# SCH_Senior_Transmitter_2026-03-29.net
KiCad netlist of a schematic drawn in EasyEDA
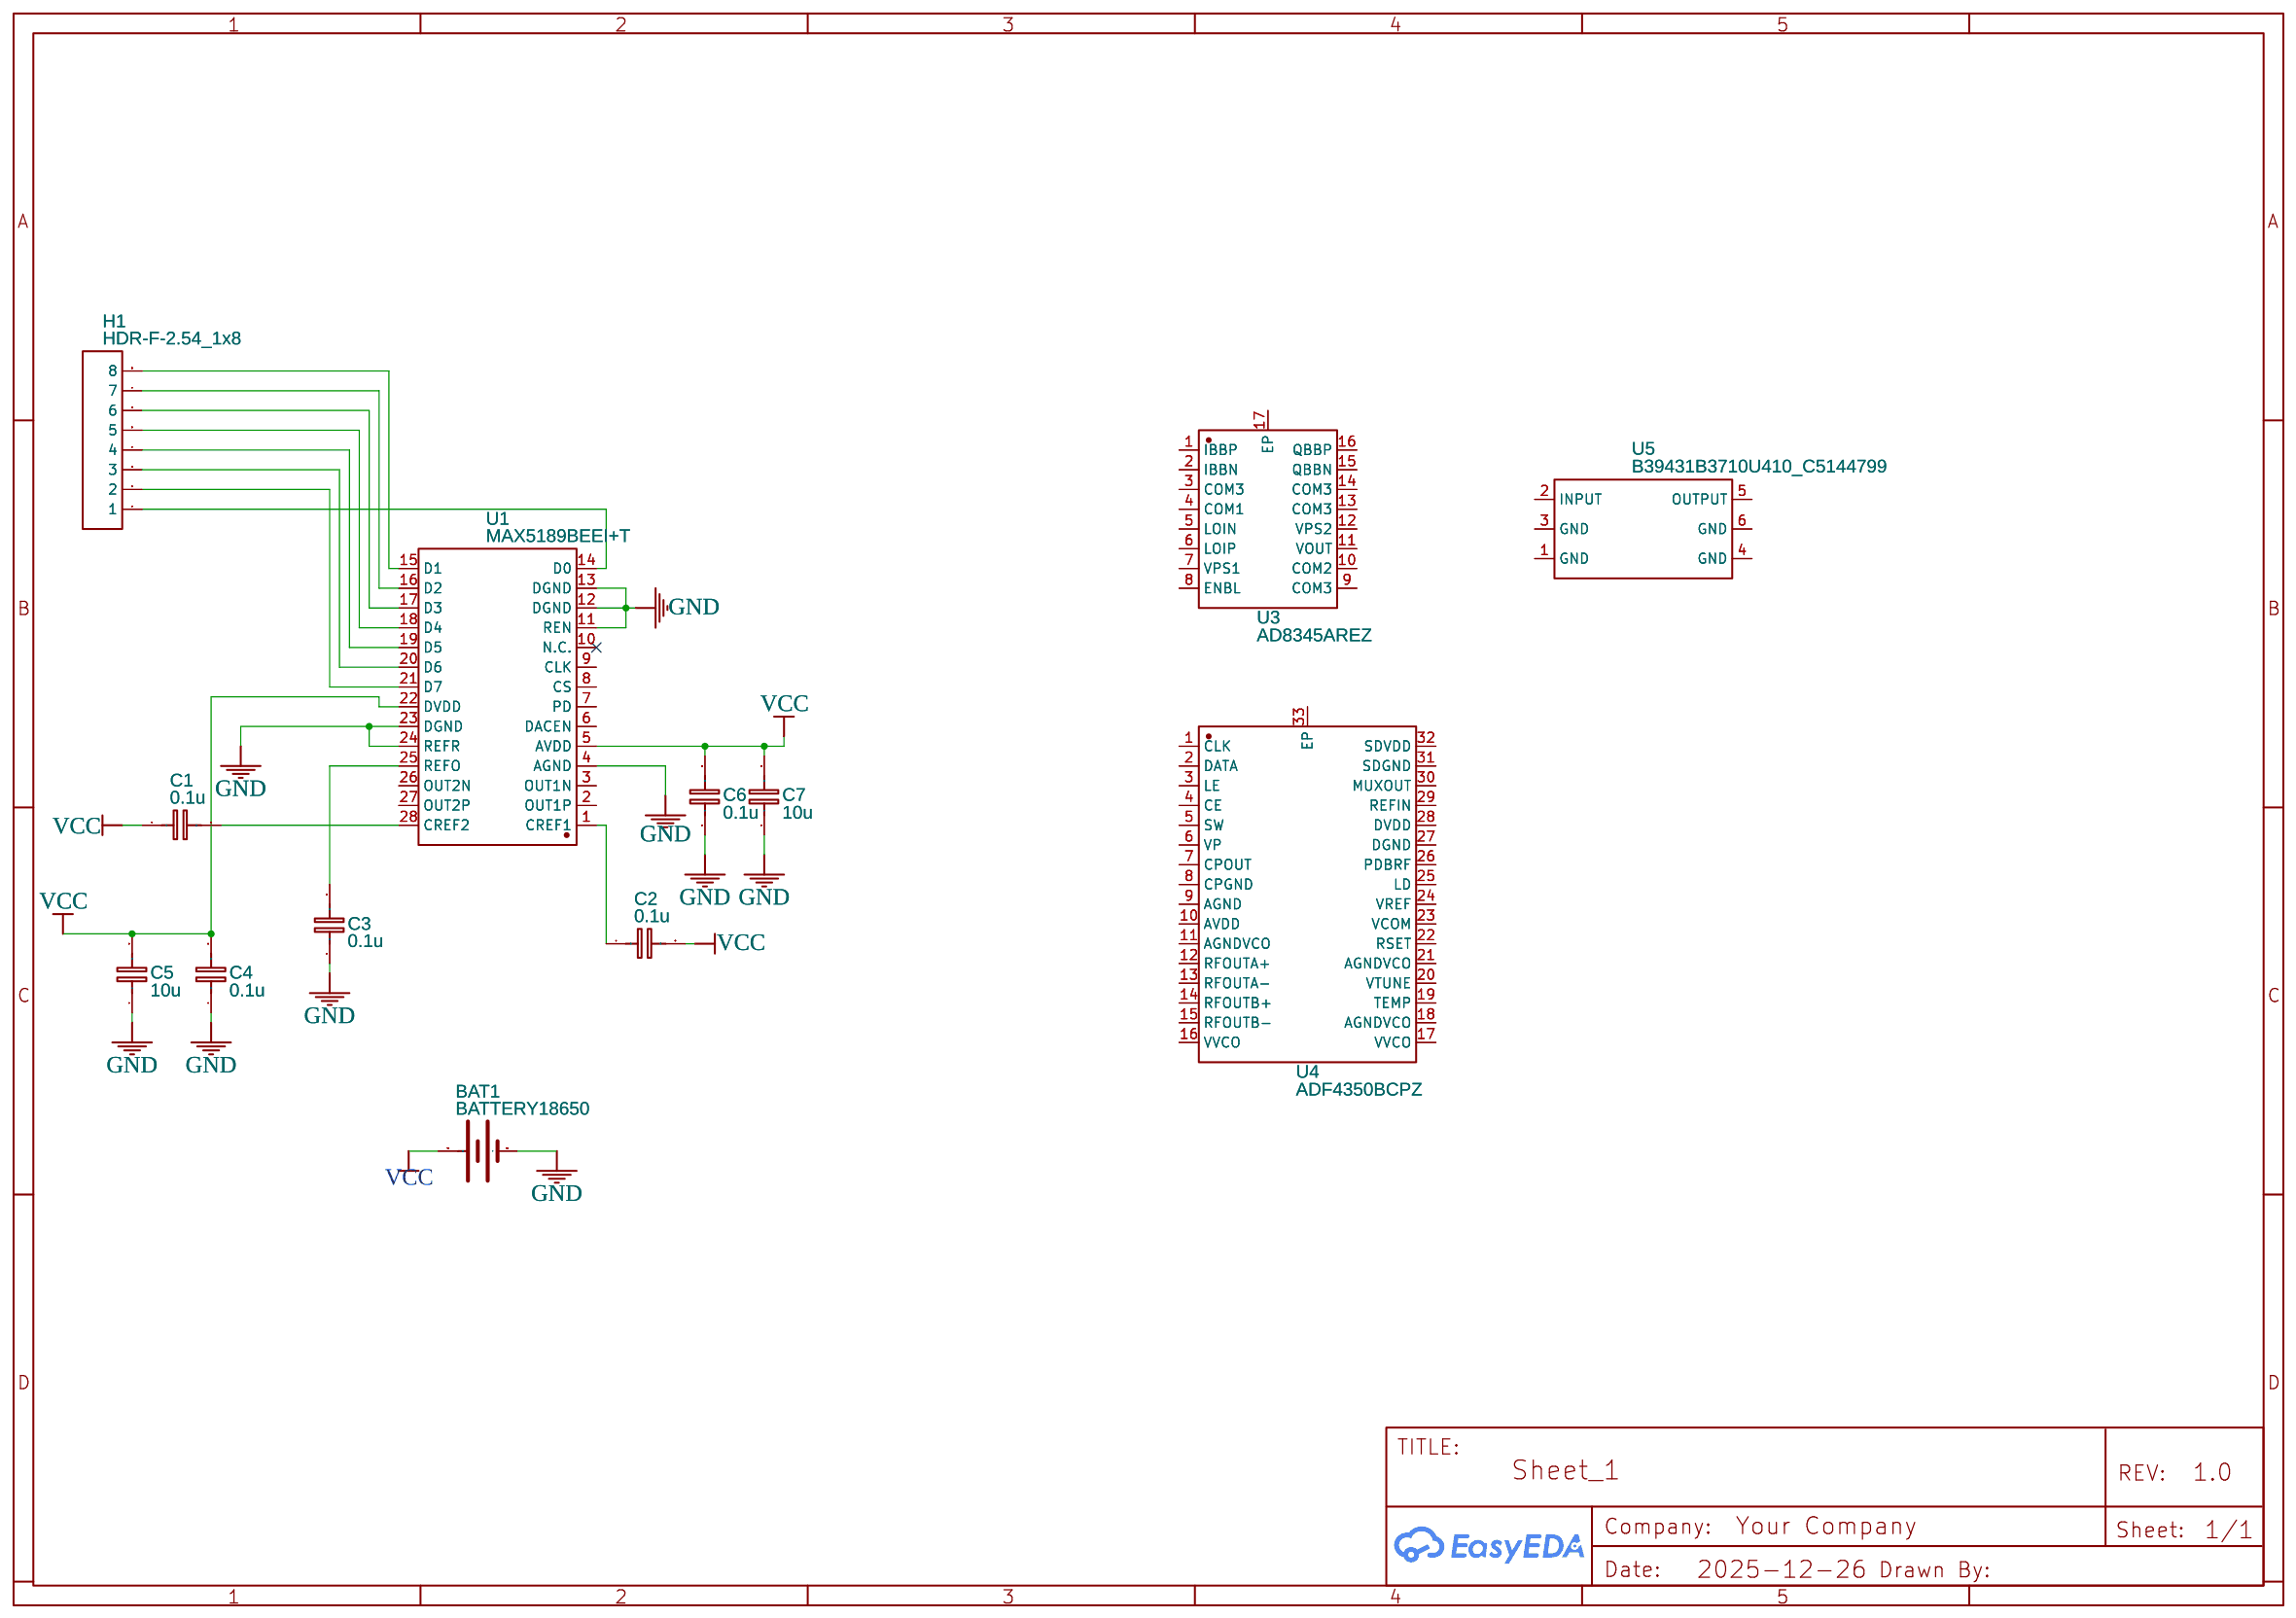
[diagram p0: schematic sheet]

(export (version "E")
  (design (tool "Eeschema 10.0.6"))
  (components
    (comp (ref "BAT1") (value "BATTERY18650") (libsource (lib "") (part "BATTERY18650")))
    (comp (ref "C1") (value "0.1u") (libsource (lib "") (part "C_0603_EU")))
    (comp (ref "C2") (value "0.1u") (libsource (lib "") (part "C_0603_EU_3")))
    (comp (ref "C3") (value "0.1u") (libsource (lib "") (part "C_0603_EU_2")))
    (comp (ref "C4") (value "0.1u") (libsource (lib "") (part "C_0603_EU_1")))
    (comp (ref "C5") (value "10u") (libsource (lib "") (part "C_0603_EU_1")))
    (comp (ref "C6") (value "0.1u") (libsource (lib "") (part "C_0603_EU_2")))
    (comp (ref "C7") (value "10u") (libsource (lib "") (part "C_0603_EU_2")))
    (comp (ref "H1") (value "HDR-F-2.54_1x8") (libsource (lib "") (part "HDR-F-2.54_1x8")))
    (comp (ref "U1")
      (value "MAX5189BEEI+T")
      (fields (field (name "Manufacturer") "ADI(亚德诺)/MAXIM(美信)"))
      (libsource (lib "") (part "MAX5189BEEI+T"))
    )
    (comp (ref "U3")
      (value "AD8345AREZ")
      (fields (field (name "Manufacturer") "ADI(亚德诺)"))
      (libsource (lib "") (part "AD8345AREZ"))
    )
    (comp (ref "U4")
      (value "ADF4350BCPZ")
      (fields (field (name "Manufacturer") "ADI(亚德诺)"))
      (libsource (lib "") (part "ADF4350BCPZ"))
    )
    (comp (ref "U5")
      (value "B39431B3710U410_C5144799")
      (fields (field (name "Manufacturer Part") "B39431B3710U410"))
      (libsource (lib "") (part "B39431B3710U410_C5144799"))
    )
  )
  (nets
    (net (code "1") (name "GND") (class "Default")
      (node (ref "BAT1") (pin "GND@1") (pinfunction "-_GND@1") (pintype "passive"))
      (node (ref "C3") (pin "1") (pinfunction "1_1") (pintype "unspecified"))
      (node (ref "C4") (pin "1") (pinfunction "1_1") (pintype "unspecified"))
      (node (ref "C5") (pin "1") (pinfunction "1_1") (pintype "unspecified"))
      (node (ref "C6") (pin "1") (pinfunction "1_1") (pintype "unspecified"))
      (node (ref "C7") (pin "1") (pinfunction "1_1") (pintype "unspecified"))
      (node (ref "U1") (pin "11") (pinfunction "REN_11") (pintype "unspecified"))
      (node (ref "U1") (pin "12") (pinfunction "DGND_12") (pintype "unspecified"))
      (node (ref "U1") (pin "13") (pinfunction "DGND_13") (pintype "unspecified"))
      (node (ref "U1") (pin "23") (pinfunction "DGND_23") (pintype "unspecified"))
      (node (ref "U1") (pin "24") (pinfunction "REFR_24") (pintype "unspecified"))
      (node (ref "U1") (pin "4") (pinfunction "AGND_4") (pintype "unspecified"))
    )
    (net (code "2") (name "Net-(U1-CREF1)") (class "Default")
      (node (ref "C2") (pin "1") (pinfunction "1_1") (pintype "unspecified"))
      (node (ref "U1") (pin "1") (pinfunction "CREF1_1") (pintype "unspecified"))
    )
    (net (code "3") (name "Net-(U1-CREF2)") (class "Default")
      (node (ref "C1") (pin "2") (pinfunction "2_2") (pintype "unspecified"))
      (node (ref "U1") (pin "28") (pinfunction "CREF2_28") (pintype "unspecified"))
    )
    (net (code "4") (name "Net-(U1-D0)") (class "Default")
      (node (ref "H1") (pin "1") (pinfunction "1_1") (pintype "unspecified"))
      (node (ref "U1") (pin "14") (pinfunction "D0_14") (pintype "unspecified"))
    )
    (net (code "5") (name "Net-(U1-D1)") (class "Default")
      (node (ref "H1") (pin "8") (pinfunction "8_8") (pintype "unspecified"))
      (node (ref "U1") (pin "15") (pinfunction "D1_15") (pintype "unspecified"))
    )
    (net (code "6") (name "Net-(U1-D2)") (class "Default")
      (node (ref "H1") (pin "7") (pinfunction "7_7") (pintype "unspecified"))
      (node (ref "U1") (pin "16") (pinfunction "D2_16") (pintype "unspecified"))
    )
    (net (code "7") (name "Net-(U1-D3)") (class "Default")
      (node (ref "H1") (pin "6") (pinfunction "6_6") (pintype "unspecified"))
      (node (ref "U1") (pin "17") (pinfunction "D3_17") (pintype "unspecified"))
    )
    (net (code "8") (name "Net-(U1-D4)") (class "Default")
      (node (ref "H1") (pin "5") (pinfunction "5_5") (pintype "unspecified"))
      (node (ref "U1") (pin "18") (pinfunction "D4_18") (pintype "unspecified"))
    )
    (net (code "9") (name "Net-(U1-D5)") (class "Default")
      (node (ref "H1") (pin "4") (pinfunction "4_4") (pintype "unspecified"))
      (node (ref "U1") (pin "19") (pinfunction "D5_19") (pintype "unspecified"))
    )
    (net (code "10") (name "Net-(U1-D6)") (class "Default")
      (node (ref "H1") (pin "3") (pinfunction "3_3") (pintype "unspecified"))
      (node (ref "U1") (pin "20") (pinfunction "D6_20") (pintype "unspecified"))
    )
    (net (code "11") (name "Net-(U1-D7)") (class "Default")
      (node (ref "H1") (pin "2") (pinfunction "2_2") (pintype "unspecified"))
      (node (ref "U1") (pin "21") (pinfunction "D7_21") (pintype "unspecified"))
    )
    (net (code "12") (name "Net-(U1-REFO)") (class "Default")
      (node (ref "C3") (pin "2") (pinfunction "2_2") (pintype "unspecified"))
      (node (ref "U1") (pin "25") (pinfunction "REFO_25") (pintype "unspecified"))
    )
    (net (code "13") (name "VCC") (class "Default")
      (node (ref "BAT1") (pin "PWR@1") (pinfunction "+_PWR@1") (pintype "passive"))
      (node (ref "C1") (pin "1") (pinfunction "1_1") (pintype "unspecified"))
      (node (ref "C2") (pin "2") (pinfunction "2_2") (pintype "unspecified"))
      (node (ref "C4") (pin "2") (pinfunction "2_2") (pintype "unspecified"))
      (node (ref "C5") (pin "2") (pinfunction "2_2") (pintype "unspecified"))
      (node (ref "C6") (pin "2") (pinfunction "2_2") (pintype "unspecified"))
      (node (ref "C7") (pin "2") (pinfunction "2_2") (pintype "unspecified"))
      (node (ref "U1") (pin "22") (pinfunction "DVDD_22") (pintype "unspecified"))
      (node (ref "U1") (pin "5") (pinfunction "AVDD_5") (pintype "unspecified"))
    )
    (net (code "14") (name "unconnected-(U1-CLK-Pad9)") (class "Default")
      (node (ref "U1") (pin "9") (pinfunction "CLK_9") (pintype "unspecified"))
    )
    (net (code "15") (name "unconnected-(U1-CS-Pad8)") (class "Default")
      (node (ref "U1") (pin "8") (pinfunction "CS_8") (pintype "unspecified"))
    )
    (net (code "16") (name "unconnected-(U1-DACEN-Pad6)") (class "Default")
      (node (ref "U1") (pin "6") (pinfunction "DACEN_6") (pintype "unspecified"))
    )
    (net (code "17") (name "unconnected-(U1-N.C.-Pad10)") (class "Default")
      (node (ref "U1") (pin "10") (pinfunction "N.C._10") (pintype "unspecified+no_connect"))
    )
    (net (code "18") (name "unconnected-(U1-OUT1N-Pad3)") (class "Default")
      (node (ref "U1") (pin "3") (pinfunction "OUT1N_3") (pintype "unspecified"))
    )
    (net (code "19") (name "unconnected-(U1-OUT1P-Pad2)") (class "Default")
      (node (ref "U1") (pin "2") (pinfunction "OUT1P_2") (pintype "unspecified"))
    )
    (net (code "20") (name "unconnected-(U1-OUT2N-Pad26)") (class "Default")
      (node (ref "U1") (pin "26") (pinfunction "OUT2N_26") (pintype "unspecified"))
    )
    (net (code "21") (name "unconnected-(U1-OUT2P-Pad27)") (class "Default")
      (node (ref "U1") (pin "27") (pinfunction "OUT2P_27") (pintype "unspecified"))
    )
    (net (code "22") (name "unconnected-(U1-PD-Pad7)") (class "Default")
      (node (ref "U1") (pin "7") (pinfunction "PD_7") (pintype "unspecified"))
    )
    (net (code "23") (name "unconnected-(U3-COM1-Pad4)") (class "Default")
      (node (ref "U3") (pin "4") (pinfunction "COM1_4") (pintype "unspecified"))
    )
    (net (code "24") (name "unconnected-(U3-COM2-Pad10)") (class "Default")
      (node (ref "U3") (pin "10") (pinfunction "COM2_10") (pintype "unspecified"))
    )
    (net (code "25") (name "unconnected-(U3-COM3-Pad3)") (class "Default")
      (node (ref "U3") (pin "3") (pinfunction "COM3_3") (pintype "unspecified"))
    )
    (net (code "26") (name "unconnected-(U3-COM3-Pad9)") (class "Default")
      (node (ref "U3") (pin "9") (pinfunction "COM3_9") (pintype "unspecified"))
    )
    (net (code "27") (name "unconnected-(U3-COM3-Pad13)") (class "Default")
      (node (ref "U3") (pin "13") (pinfunction "COM3_13") (pintype "unspecified"))
    )
    (net (code "28") (name "unconnected-(U3-COM3-Pad14)") (class "Default")
      (node (ref "U3") (pin "14") (pinfunction "COM3_14") (pintype "unspecified"))
    )
    (net (code "29") (name "unconnected-(U3-ENBL-Pad8)") (class "Default")
      (node (ref "U3") (pin "8") (pinfunction "ENBL_8") (pintype "unspecified"))
    )
    (net (code "30") (name "unconnected-(U3-EP-Pad17)") (class "Default")
      (node (ref "U3") (pin "17") (pinfunction "EP_17") (pintype "unspecified"))
    )
    (net (code "31") (name "unconnected-(U3-IBBN-Pad2)") (class "Default")
      (node (ref "U3") (pin "2") (pinfunction "IBBN_2") (pintype "unspecified"))
    )
    (net (code "32") (name "unconnected-(U3-IBBP-Pad1)") (class "Default")
      (node (ref "U3") (pin "1") (pinfunction "IBBP_1") (pintype "unspecified"))
    )
    (net (code "33") (name "unconnected-(U3-LOIN-Pad5)") (class "Default")
      (node (ref "U3") (pin "5") (pinfunction "LOIN_5") (pintype "unspecified"))
    )
    (net (code "34") (name "unconnected-(U3-LOIP-Pad6)") (class "Default")
      (node (ref "U3") (pin "6") (pinfunction "LOIP_6") (pintype "unspecified"))
    )
    (net (code "35") (name "unconnected-(U3-QBBN-Pad15)") (class "Default")
      (node (ref "U3") (pin "15") (pinfunction "QBBN_15") (pintype "unspecified"))
    )
    (net (code "36") (name "unconnected-(U3-QBBP-Pad16)") (class "Default")
      (node (ref "U3") (pin "16") (pinfunction "QBBP_16") (pintype "unspecified"))
    )
    (net (code "37") (name "unconnected-(U3-VOUT-Pad11)") (class "Default")
      (node (ref "U3") (pin "11") (pinfunction "VOUT_11") (pintype "unspecified"))
    )
    (net (code "38") (name "unconnected-(U3-VPS1-Pad7)") (class "Default")
      (node (ref "U3") (pin "7") (pinfunction "VPS1_7") (pintype "unspecified"))
    )
    (net (code "39") (name "unconnected-(U3-VPS2-Pad12)") (class "Default")
      (node (ref "U3") (pin "12") (pinfunction "VPS2_12") (pintype "unspecified"))
    )
    (net (code "40") (name "unconnected-(U4-AGND-Pad9)") (class "Default")
      (node (ref "U4") (pin "9") (pinfunction "AGND_9") (pintype "unspecified"))
    )
    (net (code "41") (name "unconnected-(U4-AGNDVCO-Pad11)") (class "Default")
      (node (ref "U4") (pin "11") (pinfunction "AGNDVCO_11") (pintype "unspecified"))
    )
    (net (code "42") (name "unconnected-(U4-AGNDVCO-Pad18)") (class "Default")
      (node (ref "U4") (pin "18") (pinfunction "AGNDVCO_18") (pintype "unspecified"))
    )
    (net (code "43") (name "unconnected-(U4-AGNDVCO-Pad21)") (class "Default")
      (node (ref "U4") (pin "21") (pinfunction "AGNDVCO_21") (pintype "unspecified"))
    )
    (net (code "44") (name "unconnected-(U4-AVDD-Pad10)") (class "Default")
      (node (ref "U4") (pin "10") (pinfunction "AVDD_10") (pintype "unspecified"))
    )
    (net (code "45") (name "unconnected-(U4-CE-Pad4)") (class "Default")
      (node (ref "U4") (pin "4") (pinfunction "CE_4") (pintype "unspecified"))
    )
    (net (code "46") (name "unconnected-(U4-CLK-Pad1)") (class "Default")
      (node (ref "U4") (pin "1") (pinfunction "CLK_1") (pintype "unspecified"))
    )
    (net (code "47") (name "unconnected-(U4-CPGND-Pad8)") (class "Default")
      (node (ref "U4") (pin "8") (pinfunction "CPGND_8") (pintype "unspecified"))
    )
    (net (code "48") (name "unconnected-(U4-CPOUT-Pad7)") (class "Default")
      (node (ref "U4") (pin "7") (pinfunction "CPOUT_7") (pintype "unspecified"))
    )
    (net (code "49") (name "unconnected-(U4-DATA-Pad2)") (class "Default")
      (node (ref "U4") (pin "2") (pinfunction "DATA_2") (pintype "unspecified"))
    )
    (net (code "50") (name "unconnected-(U4-DGND-Pad27)") (class "Default")
      (node (ref "U4") (pin "27") (pinfunction "DGND_27") (pintype "unspecified"))
    )
    (net (code "51") (name "unconnected-(U4-DVDD-Pad28)") (class "Default")
      (node (ref "U4") (pin "28") (pinfunction "DVDD_28") (pintype "unspecified"))
    )
    (net (code "52") (name "unconnected-(U4-EP-Pad33)") (class "Default")
      (node (ref "U4") (pin "33") (pinfunction "EP_33") (pintype "unspecified"))
    )
    (net (code "53") (name "unconnected-(U4-LD-Pad25)") (class "Default")
      (node (ref "U4") (pin "25") (pinfunction "LD_25") (pintype "unspecified"))
    )
    (net (code "54") (name "unconnected-(U4-LE-Pad3)") (class "Default")
      (node (ref "U4") (pin "3") (pinfunction "LE_3") (pintype "unspecified"))
    )
    (net (code "55") (name "unconnected-(U4-MUXOUT-Pad30)") (class "Default")
      (node (ref "U4") (pin "30") (pinfunction "MUXOUT_30") (pintype "unspecified"))
    )
    (net (code "56") (name "unconnected-(U4-PDBRF-Pad26)") (class "Default")
      (node (ref "U4") (pin "26") (pinfunction "PDBRF_26") (pintype "unspecified"))
    )
    (net (code "57") (name "unconnected-(U4-REFIN-Pad29)") (class "Default")
      (node (ref "U4") (pin "29") (pinfunction "REFIN_29") (pintype "unspecified"))
    )
    (net (code "58") (name "unconnected-(U4-RFOUTA+-Pad12)") (class "Default")
      (node (ref "U4") (pin "12") (pinfunction "RFOUTA+_12") (pintype "unspecified"))
    )
    (net (code "59") (name "unconnected-(U4-RFOUTA--Pad13)") (class "Default")
      (node (ref "U4") (pin "13") (pinfunction "RFOUTA-_13") (pintype "unspecified"))
    )
    (net (code "60") (name "unconnected-(U4-RFOUTB+-Pad14)") (class "Default")
      (node (ref "U4") (pin "14") (pinfunction "RFOUTB+_14") (pintype "unspecified"))
    )
    (net (code "61") (name "unconnected-(U4-RFOUTB--Pad15)") (class "Default")
      (node (ref "U4") (pin "15") (pinfunction "RFOUTB-_15") (pintype "unspecified"))
    )
    (net (code "62") (name "unconnected-(U4-RSET-Pad22)") (class "Default")
      (node (ref "U4") (pin "22") (pinfunction "RSET_22") (pintype "unspecified"))
    )
    (net (code "63") (name "unconnected-(U4-SDGND-Pad31)") (class "Default")
      (node (ref "U4") (pin "31") (pinfunction "SDGND_31") (pintype "unspecified"))
    )
    (net (code "64") (name "unconnected-(U4-SDVDD-Pad32)") (class "Default")
      (node (ref "U4") (pin "32") (pinfunction "SDVDD_32") (pintype "unspecified"))
    )
    (net (code "65") (name "unconnected-(U4-SW-Pad5)") (class "Default")
      (node (ref "U4") (pin "5") (pinfunction "SW_5") (pintype "unspecified"))
    )
    (net (code "66") (name "unconnected-(U4-TEMP-Pad19)") (class "Default")
      (node (ref "U4") (pin "19") (pinfunction "TEMP_19") (pintype "unspecified"))
    )
    (net (code "67") (name "unconnected-(U4-VCOM-Pad23)") (class "Default")
      (node (ref "U4") (pin "23") (pinfunction "VCOM_23") (pintype "unspecified"))
    )
    (net (code "68") (name "unconnected-(U4-VP-Pad6)") (class "Default")
      (node (ref "U4") (pin "6") (pinfunction "VP_6") (pintype "unspecified"))
    )
    (net (code "69") (name "unconnected-(U4-VREF-Pad24)") (class "Default")
      (node (ref "U4") (pin "24") (pinfunction "VREF_24") (pintype "unspecified"))
    )
    (net (code "70") (name "unconnected-(U4-VTUNE-Pad20)") (class "Default")
      (node (ref "U4") (pin "20") (pinfunction "VTUNE_20") (pintype "unspecified"))
    )
    (net (code "71") (name "unconnected-(U4-VVCO-Pad16)") (class "Default")
      (node (ref "U4") (pin "16") (pinfunction "VVCO_16") (pintype "unspecified"))
    )
    (net (code "72") (name "unconnected-(U4-VVCO-Pad17)") (class "Default")
      (node (ref "U4") (pin "17") (pinfunction "VVCO_17") (pintype "unspecified"))
    )
    (net (code "73") (name "unconnected-(U5-GND-Pad1)") (class "Default")
      (node (ref "U5") (pin "1") (pinfunction "GND_1") (pintype "unspecified"))
    )
    (net (code "74") (name "unconnected-(U5-GND-Pad3)") (class "Default")
      (node (ref "U5") (pin "3") (pinfunction "GND_3") (pintype "unspecified"))
    )
    (net (code "75") (name "unconnected-(U5-GND-Pad4)") (class "Default")
      (node (ref "U5") (pin "4") (pinfunction "GND_4") (pintype "unspecified"))
    )
    (net (code "76") (name "unconnected-(U5-GND-Pad6)") (class "Default")
      (node (ref "U5") (pin "6") (pinfunction "GND_6") (pintype "unspecified"))
    )
    (net (code "77") (name "unconnected-(U5-INPUT-Pad2)") (class "Default")
      (node (ref "U5") (pin "2") (pinfunction "INPUT_2") (pintype "unspecified"))
    )
    (net (code "78") (name "unconnected-(U5-OUTPUT-Pad5)") (class "Default")
      (node (ref "U5") (pin "5") (pinfunction "OUTPUT_5") (pintype "unspecified"))
    )
  )
)
